# WallSwitch.net
KiCad netlist of a schematic drawn in EAGLE
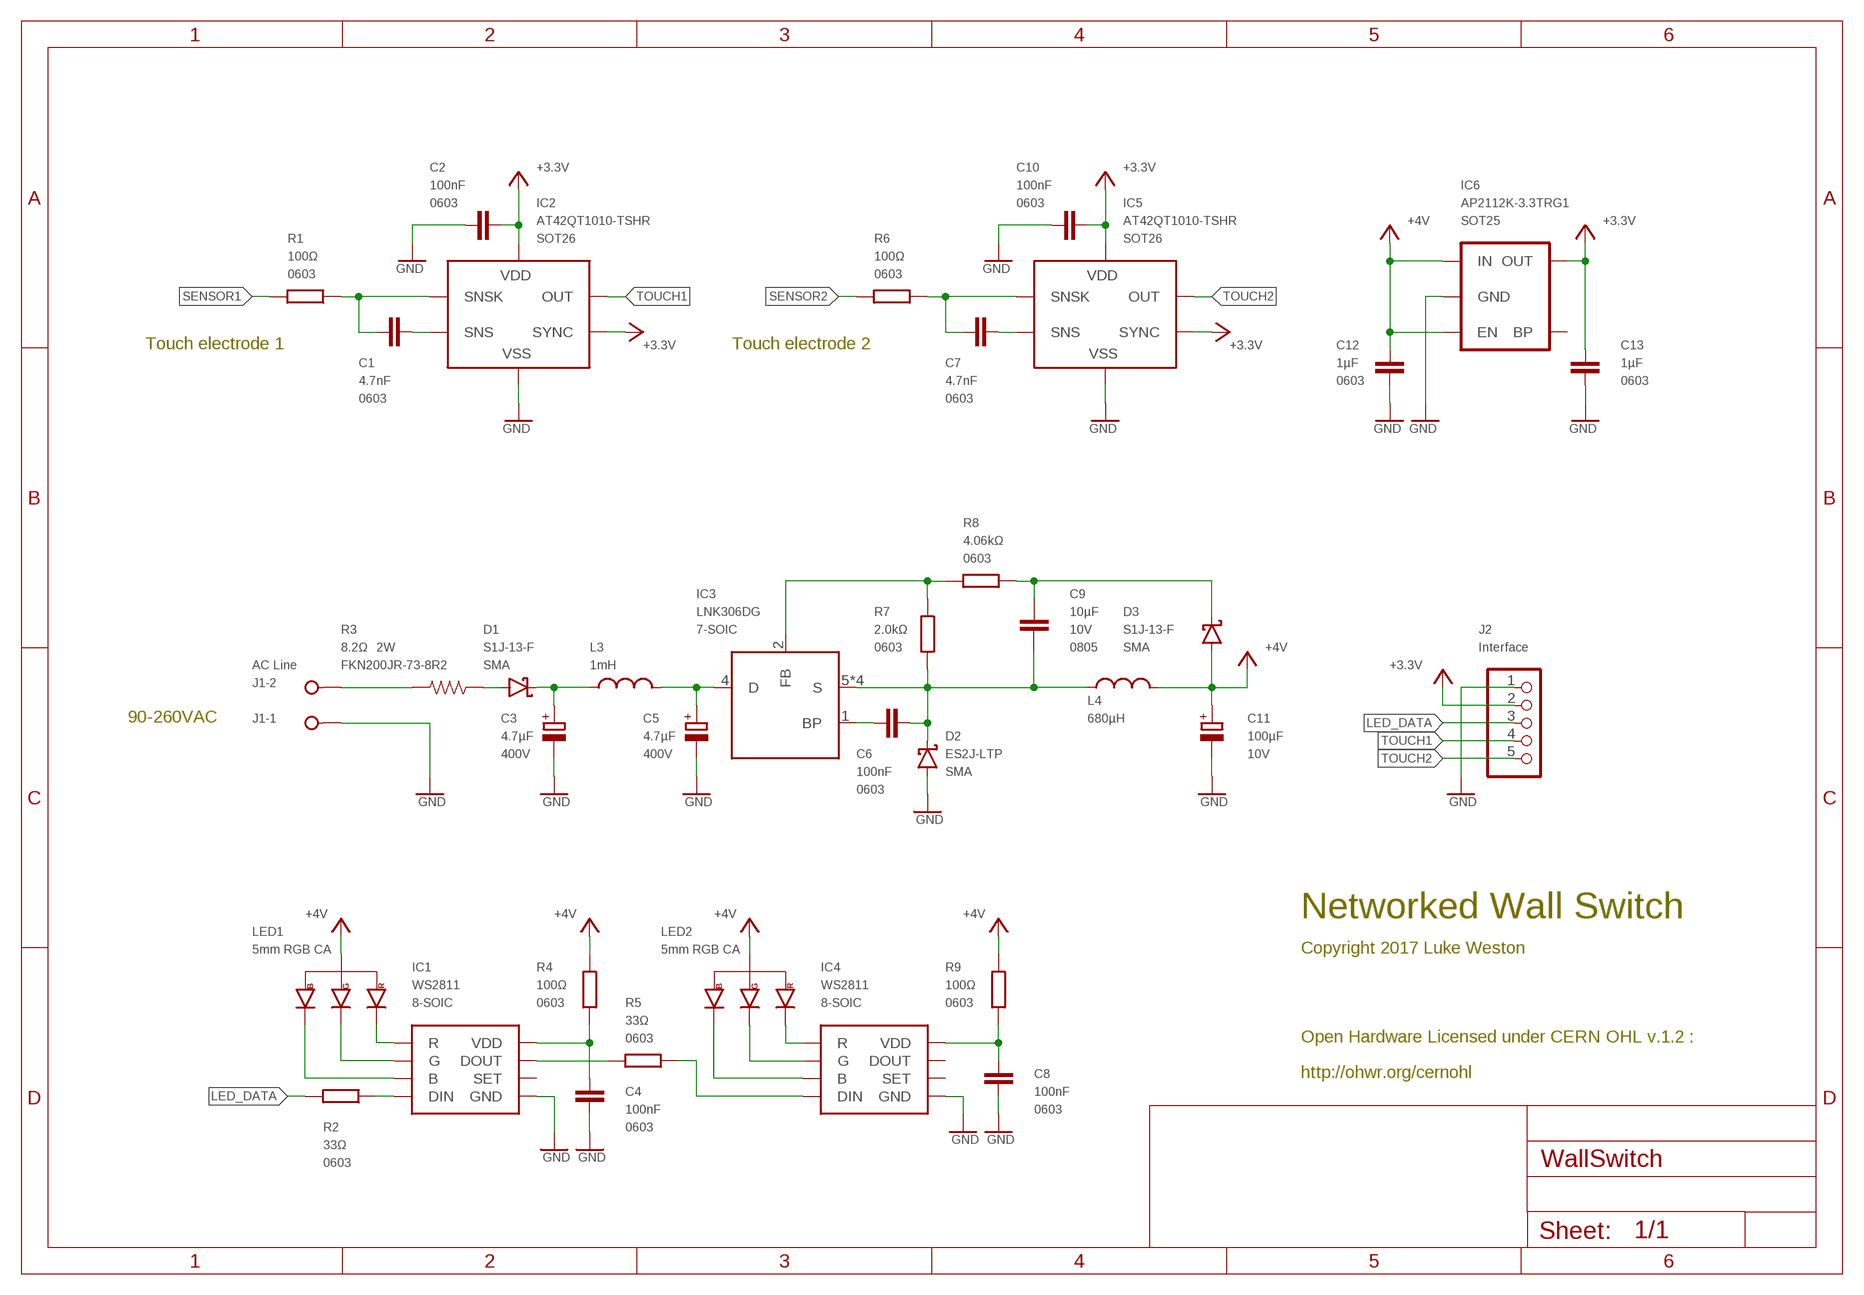
[diagram p0: schematic, sheet 1]

(export (version "E")
  (design (tool "Eeschema 10.0.6"))
  (components
    (comp (ref "C1")
      (value "4.7nF")
      (footprint "eagle-import:0603")
      (fields (field (name "PACKAGE") "0603"))
      (libsource (lib "eagle-import") (part "C0603"))
    )
    (comp (ref "C2")
      (value "100nF")
      (footprint "eagle-import:0603")
      (fields (field (name "PACKAGE") "0603"))
      (libsource (lib "eagle-import") (part "C0603"))
    )
    (comp (ref "C3")
      (value "4.7µF")
      (footprint "eagle-import:ELECTRO-LARGE")
      (fields (field (name "VOLTAGE") "400V"))
      (libsource (lib "eagle-import") (part "ELECTROLYTIC3.5MM"))
    )
    (comp (ref "C4")
      (value "100nF")
      (footprint "eagle-import:0603")
      (fields (field (name "PACKAGE") "0603"))
      (libsource (lib "eagle-import") (part "C0603"))
    )
    (comp (ref "C5")
      (value "4.7µF")
      (footprint "eagle-import:ELECTRO-LARGE")
      (fields (field (name "VOLTAGE") "400V"))
      (libsource (lib "eagle-import") (part "ELECTROLYTIC3.5MM"))
    )
    (comp (ref "C6")
      (value "100nF")
      (footprint "eagle-import:0603")
      (fields (field (name "PACKAGE") "0603"))
      (libsource (lib "eagle-import") (part "C0603"))
    )
    (comp (ref "C7")
      (value "4.7nF")
      (footprint "eagle-import:0603")
      (fields (field (name "PACKAGE") "0603"))
      (libsource (lib "eagle-import") (part "C0603"))
    )
    (comp (ref "C8")
      (value "100nF")
      (footprint "eagle-import:0603")
      (fields (field (name "PACKAGE") "0603"))
      (libsource (lib "eagle-import") (part "C0603"))
    )
    (comp (ref "C9")
      (value "10µF")
      (footprint "eagle-import:0805")
      (fields (field (name "PACKAGE") "0805") (field (name "VOLTAGE") "10V"))
      (libsource (lib "eagle-import") (part "CAP0805"))
    )
    (comp (ref "C10")
      (value "100nF")
      (footprint "eagle-import:0603")
      (fields (field (name "PACKAGE") "0603"))
      (libsource (lib "eagle-import") (part "C0603"))
    )
    (comp (ref "C11")
      (value "100µF")
      (footprint "eagle-import:ELECTRO-SMALL")
      (fields (field (name "VOLTAGE") "10V"))
      (libsource (lib "eagle-import") (part "ELECTROLYTIC2MM"))
    )
    (comp (ref "C12")
      (value "1µF")
      (footprint "eagle-import:0603")
      (fields (field (name "PACKAGE") "0603"))
      (libsource (lib "eagle-import") (part "C0603"))
    )
    (comp (ref "C13")
      (value "1µF")
      (footprint "eagle-import:0603")
      (fields (field (name "PACKAGE") "0603"))
      (libsource (lib "eagle-import") (part "C0603"))
    )
    (comp (ref "D1")
      (value "S1J-13-F")
      (footprint "eagle-import:SMA")
      (fields (field (name "PACKAGE") "SMA"))
      (libsource (lib "eagle-import") (part "SCHOTTKY-SMA"))
    )
    (comp (ref "D2")
      (value "ES2J-LTP")
      (footprint "eagle-import:SMA")
      (fields (field (name "PACKAGE") "SMA"))
      (libsource (lib "eagle-import") (part "SCHOTTKY-SMA"))
    )
    (comp (ref "D3")
      (value "S1J-13-F")
      (footprint "eagle-import:SMA")
      (fields (field (name "PACKAGE") "SMA"))
      (libsource (lib "eagle-import") (part "SCHOTTKY-SMA"))
    )
    (comp (ref "IC1")
      (value "WS2811")
      (footprint "eagle-import:SOIC-8")
      (fields (field (name "PACKAGE") "8-SOIC"))
      (libsource (lib "eagle-import") (part "WS2811"))
    )
    (comp (ref "IC2")
      (value "AT42QT1010-TSHR")
      (footprint "eagle-import:SOT23-6")
      (fields (field (name "PACKAGE") "SOT26"))
      (libsource (lib "eagle-import") (part "AT42QT1010-TSHR"))
    )
    (comp (ref "IC3")
      (value "LNK306DG")
      (footprint "eagle-import:SO-8C")
      (fields (field (name "PACKAGE") "7-SOIC"))
      (libsource (lib "eagle-import") (part "LNK304"))
    )
    (comp (ref "IC4")
      (value "WS2811")
      (footprint "eagle-import:SOIC-8")
      (fields (field (name "PACKAGE") "8-SOIC"))
      (libsource (lib "eagle-import") (part "WS2811"))
    )
    (comp (ref "IC5")
      (value "AT42QT1010-TSHR")
      (footprint "eagle-import:SOT23-6")
      (fields (field (name "PACKAGE") "SOT26"))
      (libsource (lib "eagle-import") (part "AT42QT1010-TSHR"))
    )
    (comp (ref "IC6")
      (value "AP2112K-3.3TRG1")
      (footprint "eagle-import:SOT23-5")
      (fields (field (name "PACKAGE") "SOT25"))
      (libsource (lib "eagle-import") (part "V_REG_LDOSMD"))
    )
    (comp (ref "J1")
      (value "AC Line")
      (footprint "eagle-import:W237-132")
      (libsource (lib "eagle-import") (part "W237-02P"))
    )
    (comp (ref "J2")
      (value "Interface")
      (footprint "eagle-import:1X05")
      (libsource (lib "eagle-import") (part "PINHD-1X5"))
    )
    (comp (ref "L3")
      (value "1mH")
      (footprint "eagle-import:RLB0608")
      (libsource (lib "eagle-import") (part "LRLB0608"))
    )
    (comp (ref "L4")
      (value "680µH")
      (footprint "eagle-import:RLB0914")
      (libsource (lib "eagle-import") (part "LRLB0914"))
    )
    (comp (ref "LED1")
      (value "5mm RGB CA")
      (footprint "eagle-import:LED5MMRGB")
      (libsource (lib "eagle-import") (part "RGBLED_CA-5MM"))
    )
    (comp (ref "LED2")
      (value "5mm RGB CA")
      (footprint "eagle-import:LED5MMRGB")
      (libsource (lib "eagle-import") (part "RGBLED_CA-5MM"))
    )
    (comp (ref "R1")
      (value "100Ω")
      (footprint "eagle-import:0603")
      (fields (field (name "PACKAGE") "0603"))
      (libsource (lib "eagle-import") (part "R0603"))
    )
    (comp (ref "R2")
      (value "33Ω")
      (footprint "eagle-import:0603")
      (fields (field (name "PACKAGE") "0603"))
      (libsource (lib "eagle-import") (part "R0603"))
    )
    (comp (ref "R3")
      (value "8.2Ω")
      (footprint "eagle-import:FKN200JR-73")
      (fields
        (field (name "FOO") "Fusible")
        (field (name "ID") "FKN200JR-73-8R2")
        (field (name "POWER") "2W")
      )
      (libsource (lib "eagle-import") (part "RESISTORFKN200JR-73"))
    )
    (comp (ref "R4")
      (value "100Ω")
      (footprint "eagle-import:0603")
      (fields (field (name "PACKAGE") "0603"))
      (libsource (lib "eagle-import") (part "R0603"))
    )
    (comp (ref "R5")
      (value "33Ω")
      (footprint "eagle-import:0603")
      (fields (field (name "PACKAGE") "0603"))
      (libsource (lib "eagle-import") (part "R0603"))
    )
    (comp (ref "R6")
      (value "100Ω")
      (footprint "eagle-import:0603")
      (fields (field (name "PACKAGE") "0603"))
      (libsource (lib "eagle-import") (part "R0603"))
    )
    (comp (ref "R7")
      (value "2.0kΩ")
      (footprint "eagle-import:0603")
      (fields (field (name "PACKAGE") "0603"))
      (libsource (lib "eagle-import") (part "R0603"))
    )
    (comp (ref "R8")
      (value "4.06kΩ")
      (footprint "eagle-import:0603")
      (fields (field (name "PACKAGE") "0603"))
      (libsource (lib "eagle-import") (part "R0603"))
    )
    (comp (ref "R9")
      (value "100Ω")
      (footprint "eagle-import:0603")
      (fields (field (name "PACKAGE") "0603"))
      (libsource (lib "eagle-import") (part "R0603"))
    )
  )
  (nets
    (net (code "1") (name "+3.3V") (class "Default")
      (node (ref "C10") (pin "1") (pinfunction "1_1") (pintype "passive"))
      (node (ref "C13") (pin "1") (pinfunction "1_1") (pintype "passive"))
      (node (ref "C2") (pin "1") (pinfunction "1_1") (pintype "passive"))
      (node (ref "IC2") (pin "5") (pinfunction "VDD_5") (pintype "bidirectional"))
      (node (ref "IC2") (pin "6") (pinfunction "SYNC_6") (pintype "bidirectional"))
      (node (ref "IC5") (pin "5") (pinfunction "VDD_5") (pintype "bidirectional"))
      (node (ref "IC5") (pin "6") (pinfunction "SYNC_6") (pintype "bidirectional"))
      (node (ref "IC6") (pin "5") (pinfunction "OUT_5") (pintype "passive"))
      (node (ref "J2") (pin "2") (pinfunction "2_2") (pintype "passive"))
    )
    (net (code "2") (name "+4V") (class "Default")
      (node (ref "C11") (pin "+") (pinfunction "+_+") (pintype "passive"))
      (node (ref "C12") (pin "1") (pinfunction "1_1") (pintype "passive"))
      (node (ref "D3") (pin "A") (pinfunction "A_A") (pintype "passive"))
      (node (ref "IC6") (pin "1") (pinfunction "IN_1") (pintype "input"))
      (node (ref "IC6") (pin "3") (pinfunction "EN_3") (pintype "input"))
      (node (ref "L4") (pin "2") (pinfunction "2_2") (pintype "bidirectional"))
      (node (ref "LED1") (pin "2") (pinfunction "VCC_2") (pintype "bidirectional"))
      (node (ref "LED2") (pin "2") (pinfunction "VCC_2") (pintype "bidirectional"))
      (node (ref "R4") (pin "1") (pinfunction "1_1") (pintype "passive"))
      (node (ref "R9") (pin "1") (pinfunction "1_1") (pintype "passive"))
    )
    (net (code "3") (name "/GND") (class "Default")
      (node (ref "C10") (pin "2") (pinfunction "2_2") (pintype "passive"))
      (node (ref "C11") (pin "-") (pinfunction "-_-") (pintype "passive"))
      (node (ref "C12") (pin "2") (pinfunction "2_2") (pintype "passive"))
      (node (ref "C13") (pin "2") (pinfunction "2_2") (pintype "passive"))
      (node (ref "C2") (pin "2") (pinfunction "2_2") (pintype "passive"))
      (node (ref "C3") (pin "-") (pinfunction "-_-") (pintype "passive"))
      (node (ref "C4") (pin "2") (pinfunction "2_2") (pintype "passive"))
      (node (ref "C5") (pin "-") (pinfunction "-_-") (pintype "passive"))
      (node (ref "C8") (pin "2") (pinfunction "2_2") (pintype "passive"))
      (node (ref "D2") (pin "A") (pinfunction "A_A") (pintype "passive"))
      (node (ref "IC1") (pin "4") (pinfunction "GND_4") (pintype "passive"))
      (node (ref "IC2") (pin "2") (pinfunction "VSS_2") (pintype "bidirectional"))
      (node (ref "IC4") (pin "4") (pinfunction "GND_4") (pintype "passive"))
      (node (ref "IC5") (pin "2") (pinfunction "VSS_2") (pintype "bidirectional"))
      (node (ref "IC6") (pin "2") (pinfunction "GND_2") (pintype "input"))
      (node (ref "J1") (pin "1") (pinfunction "KL_1") (pintype "passive"))
      (node (ref "J2") (pin "1") (pinfunction "1_1") (pintype "passive"))
    )
    (net (code "4") (name "LED_DATA") (class "Default")
      (node (ref "J2") (pin "3") (pinfunction "3_3") (pintype "passive"))
      (node (ref "R2") (pin "2") (pinfunction "2_2") (pintype "passive"))
    )
    (net (code "5") (name "Net-(C3-Pad+)") (class "Default")
      (node (ref "C3") (pin "+") (pinfunction "+_+") (pintype "passive"))
      (node (ref "D1") (pin "K") (pinfunction "K_K") (pintype "passive"))
      (node (ref "L3") (pin "1") (pinfunction "1_1") (pintype "bidirectional"))
    )
    (net (code "6") (name "Net-(C6-Pad1)") (class "Default")
      (node (ref "C6") (pin "1") (pinfunction "1_1") (pintype "passive"))
      (node (ref "C9") (pin "1") (pinfunction "1_1") (pintype "passive"))
      (node (ref "D2") (pin "K") (pinfunction "K_K") (pintype "passive"))
      (node (ref "IC3") (pin "5") (pinfunction "S_5") (pintype "bidirectional"))
      (node (ref "IC3") (pin "6") (pinfunction "S_6") (pintype "bidirectional"))
      (node (ref "IC3") (pin "7") (pinfunction "S_7") (pintype "bidirectional"))
      (node (ref "IC3") (pin "8") (pinfunction "S_8") (pintype "bidirectional"))
      (node (ref "L4") (pin "1") (pinfunction "1_1") (pintype "bidirectional"))
      (node (ref "R7") (pin "2") (pinfunction "2_2") (pintype "passive"))
    )
    (net (code "7") (name "Net-(C9-Pad2)") (class "Default")
      (node (ref "C9") (pin "2") (pinfunction "2_2") (pintype "passive"))
      (node (ref "D3") (pin "K") (pinfunction "K_K") (pintype "passive"))
      (node (ref "R8") (pin "2") (pinfunction "2_2") (pintype "passive"))
    )
    (net (code "8") (name "Net-(D1-PadA)") (class "Default")
      (node (ref "D1") (pin "A") (pinfunction "A_A") (pintype "passive"))
      (node (ref "R3") (pin "1") (pinfunction "1_1") (pintype "bidirectional"))
    )
    (net (code "9") (name "Net-(IC1-B)") (class "Default")
      (node (ref "IC1") (pin "3") (pinfunction "B_3") (pintype "passive"))
      (node (ref "LED1") (pin "4") (pinfunction "BLUE_4") (pintype "bidirectional"))
    )
    (net (code "10") (name "Net-(IC1-DIN)") (class "Default")
      (node (ref "IC1") (pin "6") (pinfunction "DIN_6") (pintype "passive"))
      (node (ref "R2") (pin "1") (pinfunction "1_1") (pintype "passive"))
    )
    (net (code "11") (name "Net-(IC1-DOUT)") (class "Default")
      (node (ref "IC1") (pin "5") (pinfunction "DOUT_5") (pintype "passive"))
      (node (ref "R5") (pin "2") (pinfunction "2_2") (pintype "passive"))
    )
    (net (code "12") (name "Net-(IC1-G)") (class "Default")
      (node (ref "IC1") (pin "2") (pinfunction "G_2") (pintype "passive"))
      (node (ref "LED1") (pin "3") (pinfunction "GREEN_3") (pintype "bidirectional"))
    )
    (net (code "13") (name "Net-(IC1-R)") (class "Default")
      (node (ref "IC1") (pin "1") (pinfunction "R_1") (pintype "passive"))
      (node (ref "LED1") (pin "1") (pinfunction "RED_1") (pintype "bidirectional"))
    )
    (net (code "14") (name "Net-(IC1-VDD)") (class "Default")
      (node (ref "C4") (pin "1") (pinfunction "1_1") (pintype "passive"))
      (node (ref "IC1") (pin "8") (pinfunction "VDD_8") (pintype "passive"))
      (node (ref "R4") (pin "2") (pinfunction "2_2") (pintype "passive"))
    )
    (net (code "15") (name "Net-(IC2-SNS)") (class "Default")
      (node (ref "C1") (pin "1") (pinfunction "1_1") (pintype "passive"))
      (node (ref "IC2") (pin "4") (pinfunction "SNS_4") (pintype "bidirectional"))
    )
    (net (code "16") (name "Net-(IC2-SNSK)") (class "Default")
      (node (ref "C1") (pin "2") (pinfunction "2_2") (pintype "passive"))
      (node (ref "IC2") (pin "3") (pinfunction "SNSK_3") (pintype "bidirectional"))
      (node (ref "R1") (pin "1") (pinfunction "1_1") (pintype "passive"))
    )
    (net (code "17") (name "Net-(IC3-BP)") (class "Default")
      (node (ref "C6") (pin "2") (pinfunction "2_2") (pintype "passive"))
      (node (ref "IC3") (pin "1") (pinfunction "BP_1") (pintype "bidirectional"))
    )
    (net (code "18") (name "Net-(IC3-D)") (class "Default")
      (node (ref "C5") (pin "+") (pinfunction "+_+") (pintype "passive"))
      (node (ref "IC3") (pin "4") (pinfunction "D_4") (pintype "bidirectional"))
      (node (ref "L3") (pin "2") (pinfunction "2_2") (pintype "bidirectional"))
    )
    (net (code "19") (name "Net-(IC3-FB)") (class "Default")
      (node (ref "IC3") (pin "2") (pinfunction "FB_2") (pintype "bidirectional"))
      (node (ref "R7") (pin "1") (pinfunction "1_1") (pintype "passive"))
      (node (ref "R8") (pin "1") (pinfunction "1_1") (pintype "passive"))
    )
    (net (code "20") (name "Net-(IC4-B)") (class "Default")
      (node (ref "IC4") (pin "3") (pinfunction "B_3") (pintype "passive"))
      (node (ref "LED2") (pin "4") (pinfunction "BLUE_4") (pintype "bidirectional"))
    )
    (net (code "21") (name "Net-(IC4-DIN)") (class "Default")
      (node (ref "IC4") (pin "6") (pinfunction "DIN_6") (pintype "passive"))
      (node (ref "R5") (pin "1") (pinfunction "1_1") (pintype "passive"))
    )
    (net (code "22") (name "Net-(IC4-G)") (class "Default")
      (node (ref "IC4") (pin "2") (pinfunction "G_2") (pintype "passive"))
      (node (ref "LED2") (pin "3") (pinfunction "GREEN_3") (pintype "bidirectional"))
    )
    (net (code "23") (name "Net-(IC4-R)") (class "Default")
      (node (ref "IC4") (pin "1") (pinfunction "R_1") (pintype "passive"))
      (node (ref "LED2") (pin "1") (pinfunction "RED_1") (pintype "bidirectional"))
    )
    (net (code "24") (name "Net-(IC4-VDD)") (class "Default")
      (node (ref "C8") (pin "1") (pinfunction "1_1") (pintype "passive"))
      (node (ref "IC4") (pin "8") (pinfunction "VDD_8") (pintype "passive"))
      (node (ref "R9") (pin "2") (pinfunction "2_2") (pintype "passive"))
    )
    (net (code "25") (name "Net-(IC5-SNS)") (class "Default")
      (node (ref "C7") (pin "1") (pinfunction "1_1") (pintype "passive"))
      (node (ref "IC5") (pin "4") (pinfunction "SNS_4") (pintype "bidirectional"))
    )
    (net (code "26") (name "Net-(IC5-SNSK)") (class "Default")
      (node (ref "C7") (pin "2") (pinfunction "2_2") (pintype "passive"))
      (node (ref "IC5") (pin "3") (pinfunction "SNSK_3") (pintype "bidirectional"))
      (node (ref "R6") (pin "1") (pinfunction "1_1") (pintype "passive"))
    )
    (net (code "27") (name "Net-(J1B-KL)") (class "Default")
      (node (ref "J1") (pin "2") (pinfunction "KL_2") (pintype "passive"))
      (node (ref "R3") (pin "2") (pinfunction "2_2") (pintype "bidirectional"))
    )
    (net (code "28") (name "SENSOR1") (class "Default")
      (node (ref "R1") (pin "2") (pinfunction "2_2") (pintype "passive"))
    )
    (net (code "29") (name "SENSOR2") (class "Default")
      (node (ref "R6") (pin "2") (pinfunction "2_2") (pintype "passive"))
    )
    (net (code "30") (name "TOUCH1") (class "Default")
      (node (ref "IC2") (pin "1") (pinfunction "OUT_1") (pintype "bidirectional"))
      (node (ref "J2") (pin "4") (pinfunction "4_4") (pintype "passive"))
    )
    (net (code "31") (name "TOUCH2") (class "Default")
      (node (ref "IC5") (pin "1") (pinfunction "OUT_1") (pintype "bidirectional"))
      (node (ref "J2") (pin "5") (pinfunction "5_5") (pintype "passive"))
    )
    (net (code "32") (name "unconnected-(IC1-SET-Pad7)") (class "Default")
      (node (ref "IC1") (pin "7") (pinfunction "SET_7") (pintype "passive"))
    )
    (net (code "33") (name "unconnected-(IC4-DOUT-Pad5)") (class "Default")
      (node (ref "IC4") (pin "5") (pinfunction "DOUT_5") (pintype "passive"))
    )
    (net (code "34") (name "unconnected-(IC4-SET-Pad7)") (class "Default")
      (node (ref "IC4") (pin "7") (pinfunction "SET_7") (pintype "passive"))
    )
    (net (code "35") (name "unconnected-(IC6-BP-Pad4)") (class "Default")
      (node (ref "IC6") (pin "4") (pinfunction "BP_4") (pintype "input"))
    )
  )
)
